# DAC_PMOD.net
KiCad netlist of a schematic drawn in EAGLE
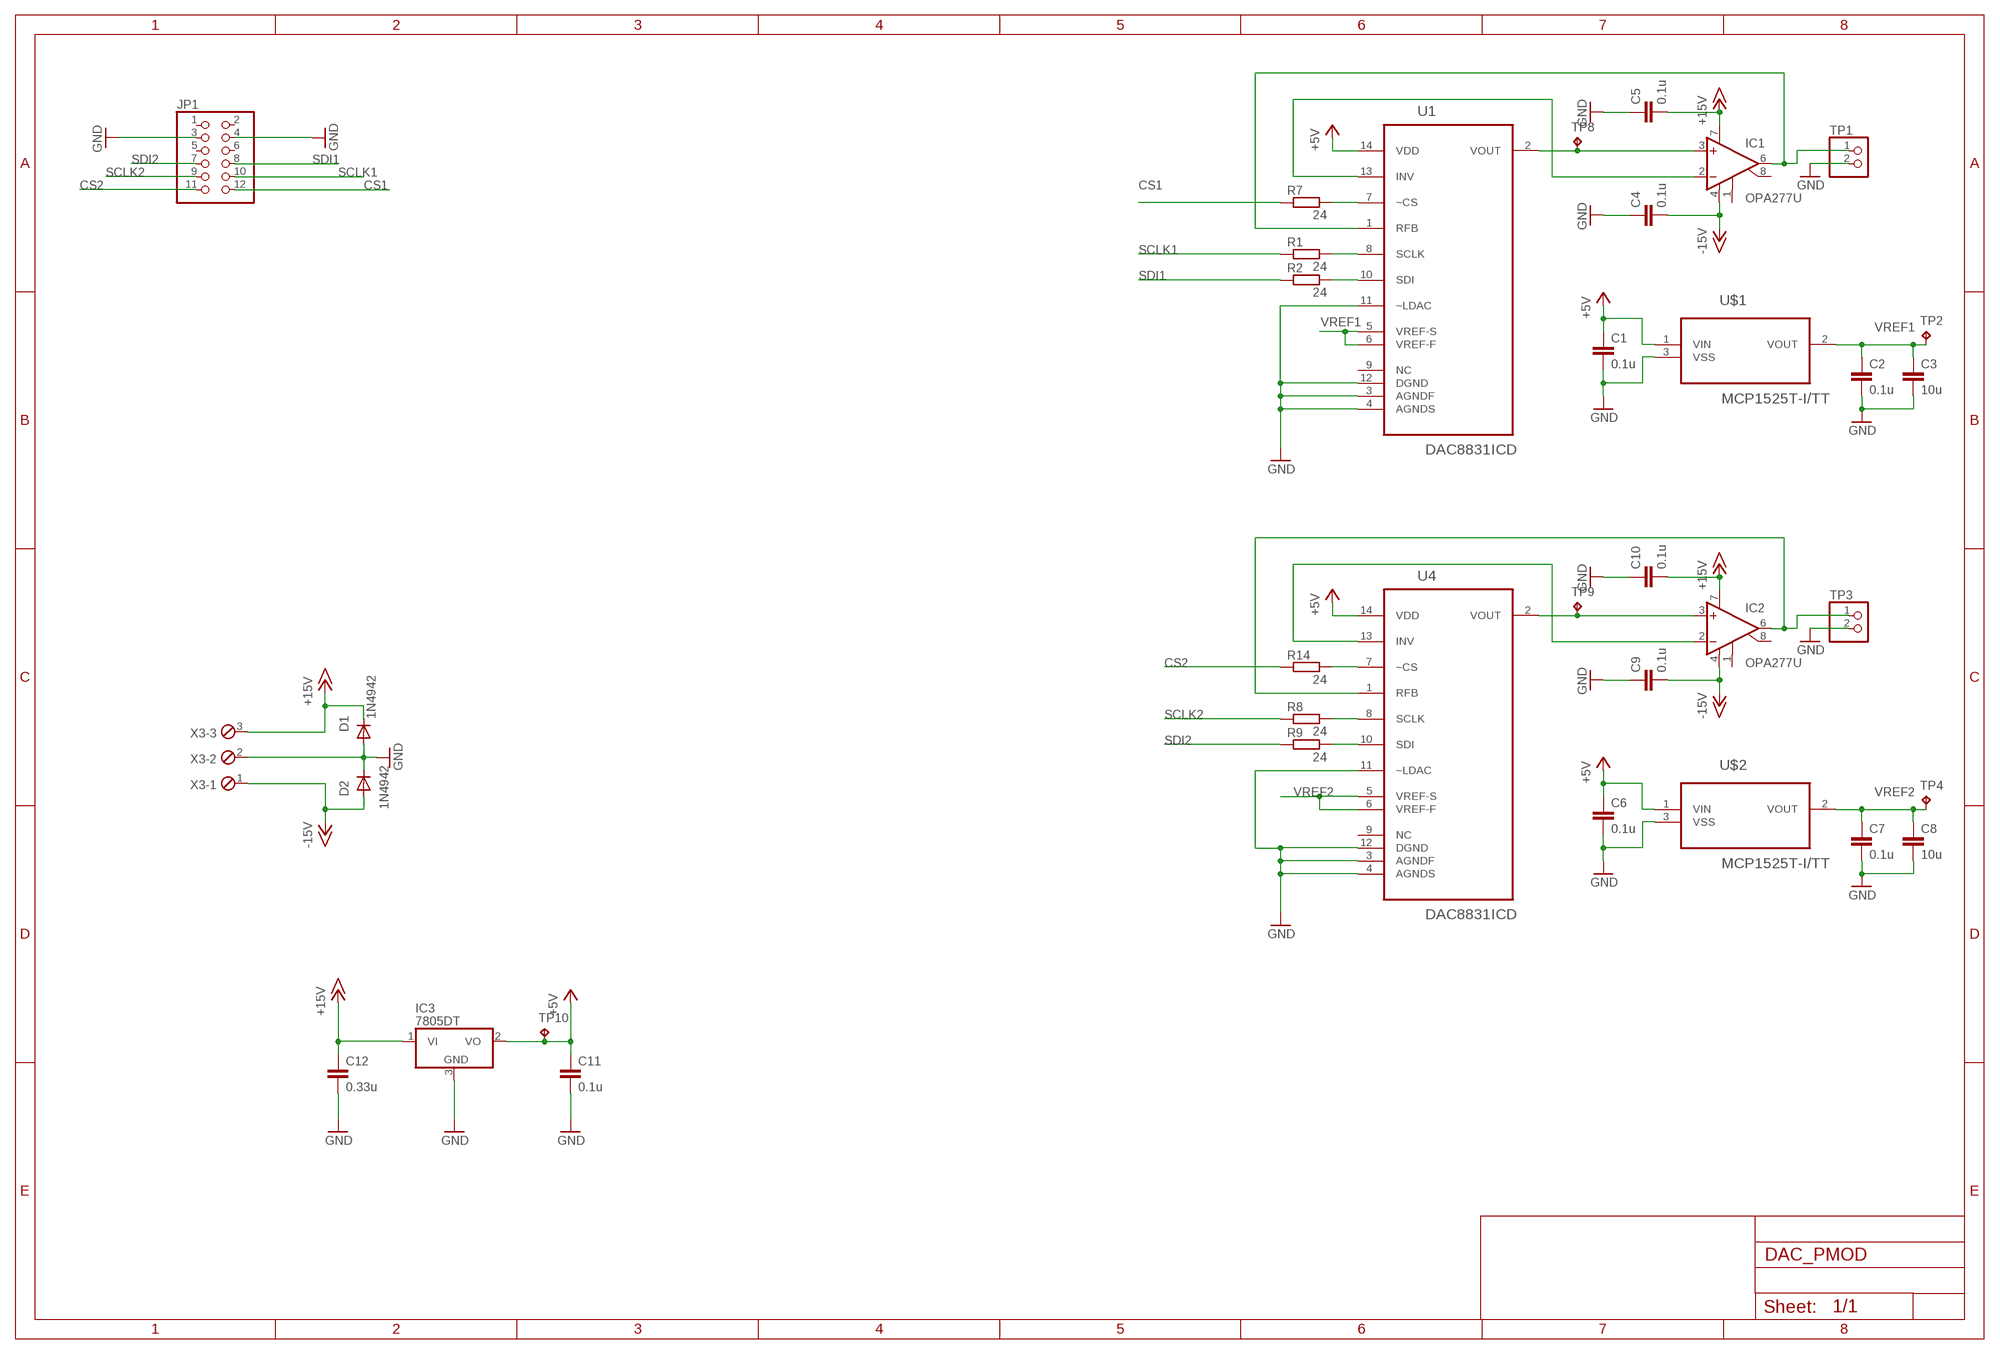
[diagram p0: schematic, sheet 1]

(export (version "E")
  (design (tool "Eeschema 10.0.6"))
  (components
    (comp (ref "C1")
      (value "0.1u")
      (footprint "eagle-import:C0603")
      (libsource (lib "eagle-import") (part "C-EUC0603"))
    )
    (comp (ref "C2")
      (value "0.1u")
      (footprint "eagle-import:C0603")
      (libsource (lib "eagle-import") (part "C-EUC0603"))
    )
    (comp (ref "C3")
      (value "10u")
      (footprint "eagle-import:C0603")
      (libsource (lib "eagle-import") (part "C-EUC0603"))
    )
    (comp (ref "C4")
      (value "0.1u")
      (footprint "eagle-import:C0603")
      (libsource (lib "eagle-import") (part "C-EUC0603"))
    )
    (comp (ref "C5")
      (value "0.1u")
      (footprint "eagle-import:C0603")
      (libsource (lib "eagle-import") (part "C-EUC0603"))
    )
    (comp (ref "C6")
      (value "0.1u")
      (footprint "eagle-import:C0603")
      (libsource (lib "eagle-import") (part "C-EUC0603"))
    )
    (comp (ref "C7")
      (value "0.1u")
      (footprint "eagle-import:C0603")
      (libsource (lib "eagle-import") (part "C-EUC0603"))
    )
    (comp (ref "C8")
      (value "10u")
      (footprint "eagle-import:C0603")
      (libsource (lib "eagle-import") (part "C-EUC0603"))
    )
    (comp (ref "C9")
      (value "0.1u")
      (footprint "eagle-import:C0603")
      (libsource (lib "eagle-import") (part "C-EUC0603"))
    )
    (comp (ref "C10")
      (value "0.1u")
      (footprint "eagle-import:C0603")
      (libsource (lib "eagle-import") (part "C-EUC0603"))
    )
    (comp (ref "C11")
      (value "0.1u")
      (footprint "eagle-import:C0603")
      (libsource (lib "eagle-import") (part "C-EUC0603"))
    )
    (comp (ref "C12")
      (value "0.33u")
      (footprint "eagle-import:C0603")
      (libsource (lib "eagle-import") (part "C-EUC0603"))
    )
    (comp (ref "D1")
      (value "1N4942")
      (footprint "eagle-import:DO41-10")
      (libsource (lib "eagle-import") (part "1N4942"))
    )
    (comp (ref "D2")
      (value "1N4942")
      (footprint "eagle-import:DO41-10")
      (libsource (lib "eagle-import") (part "1N4942"))
    )
    (comp (ref "IC1")
      (value "OPA277U")
      (footprint "eagle-import:SO08")
      (libsource (lib "eagle-import") (part "OPA277U"))
    )
    (comp (ref "IC2")
      (value "OPA277U")
      (footprint "eagle-import:SO08")
      (libsource (lib "eagle-import") (part "OPA277U"))
    )
    (comp (ref "IC3")
      (value "7805DT")
      (footprint "eagle-import:TO252")
      (libsource (lib "eagle-import") (part "78DT05"))
    )
    (comp (ref "JP1")
      (value "PINHD-2X6/90")
      (footprint "eagle-import:2X06_90")
      (libsource (lib "eagle-import") (part "PINHD-2X6/90"))
    )
    (comp (ref "R1")
      (value "24")
      (footprint "eagle-import:R0603")
      (libsource (lib "eagle-import") (part "R-EU_R0603"))
    )
    (comp (ref "R2")
      (value "24")
      (footprint "eagle-import:R0603")
      (libsource (lib "eagle-import") (part "R-EU_R0603"))
    )
    (comp (ref "R7")
      (value "24")
      (footprint "eagle-import:R0603")
      (libsource (lib "eagle-import") (part "R-EU_R0603"))
    )
    (comp (ref "R8")
      (value "24")
      (footprint "eagle-import:R0603")
      (libsource (lib "eagle-import") (part "R-EU_R0603"))
    )
    (comp (ref "R9")
      (value "24")
      (footprint "eagle-import:R0603")
      (libsource (lib "eagle-import") (part "R-EU_R0603"))
    )
    (comp (ref "R14")
      (value "24")
      (footprint "eagle-import:R0603")
      (libsource (lib "eagle-import") (part "R-EU_R0603"))
    )
    (comp (ref "TP1")
      (value "PINHD-1X2")
      (footprint "eagle-import:1X02")
      (libsource (lib "eagle-import") (part "PINHD-1X2"))
    )
    (comp (ref "TP2")
      (value "TPB1,27")
      (footprint "eagle-import:B1,27")
      (libsource (lib "eagle-import") (part "TPB1,27"))
    )
    (comp (ref "TP3")
      (value "PINHD-1X2")
      (footprint "eagle-import:1X02")
      (libsource (lib "eagle-import") (part "PINHD-1X2"))
    )
    (comp (ref "TP4")
      (value "TPB1,27")
      (footprint "eagle-import:B1,27")
      (libsource (lib "eagle-import") (part "TPB1,27"))
    )
    (comp (ref "TP8")
      (value "TPB1,27")
      (footprint "eagle-import:B1,27")
      (libsource (lib "eagle-import") (part "TPB1,27"))
    )
    (comp (ref "TP9")
      (value "TPB1,27")
      (footprint "eagle-import:B1,27")
      (libsource (lib "eagle-import") (part "TPB1,27"))
    )
    (comp (ref "TP10")
      (value "TPB1,27")
      (footprint "eagle-import:B1,27")
      (libsource (lib "eagle-import") (part "TPB1,27"))
    )
    (comp (ref "U$1")
      (value "MCP1525T-I/TT")
      (footprint "eagle-import:SOT96P237X112-3N")
      (libsource (lib "eagle-import") (part "MCP1525T-I/TT"))
    )
    (comp (ref "U$2")
      (value "MCP1525T-I/TT")
      (footprint "eagle-import:SOT96P237X112-3N")
      (libsource (lib "eagle-import") (part "MCP1525T-I/TT"))
    )
    (comp (ref "U1")
      (value "DAC8831ICD")
      (footprint "eagle-import:SOIC127P600X175-14N")
      (libsource (lib "eagle-import") (part "DAC8831ICD"))
    )
    (comp (ref "U4")
      (value "DAC8831ICD")
      (footprint "eagle-import:SOIC127P600X175-14N")
      (libsource (lib "eagle-import") (part "DAC8831ICD"))
    )
    (comp (ref "X3")
      (value "MPT3")
      (footprint "eagle-import:3POL254")
      (libsource (lib "eagle-import") (part "MPT3"))
    )
  )
  (nets
    (net (code "1") (name "+5V") (class "Default")
      (node (ref "C1") (pin "1") (pinfunction "1_1") (pintype "passive"))
      (node (ref "C11") (pin "1") (pinfunction "1_1") (pintype "passive"))
      (node (ref "C6") (pin "1") (pinfunction "1_1") (pintype "passive"))
      (node (ref "IC3") (pin "2") (pinfunction "VO_2") (pintype "passive"))
      (node (ref "TP10") (pin "TP") (pinfunction "TP_TP") (pintype "input"))
      (node (ref "U$1") (pin "1") (pinfunction "VIN_1") (pintype "power_in"))
      (node (ref "U$2") (pin "1") (pinfunction "VIN_1") (pintype "power_in"))
      (node (ref "U1") (pin "14") (pinfunction "VDD_14") (pintype "power_in"))
      (node (ref "U4") (pin "14") (pinfunction "VDD_14") (pintype "power_in"))
    )
    (net (code "2") (name "+15V") (class "Default")
      (node (ref "C10") (pin "2") (pinfunction "2_2") (pintype "passive"))
      (node (ref "C12") (pin "1") (pinfunction "1_1") (pintype "passive"))
      (node (ref "C5") (pin "2") (pinfunction "2_2") (pintype "passive"))
      (node (ref "D1") (pin "C") (pinfunction "C_C") (pintype "passive"))
      (node (ref "IC1") (pin "7") (pinfunction "V+_7") (pintype "power_in"))
      (node (ref "IC2") (pin "7") (pinfunction "V+_7") (pintype "power_in"))
      (node (ref "IC3") (pin "1") (pinfunction "VI_1") (pintype "input"))
      (node (ref "X3") (pin "3") (pinfunction "1_3") (pintype "passive"))
    )
    (net (code "3") (name "-15V") (class "Default")
      (node (ref "C4") (pin "2") (pinfunction "2_2") (pintype "passive"))
      (node (ref "C9") (pin "2") (pinfunction "2_2") (pintype "passive"))
      (node (ref "D2") (pin "A") (pinfunction "A_A") (pintype "passive"))
      (node (ref "IC1") (pin "4") (pinfunction "V-_4") (pintype "power_in"))
      (node (ref "IC2") (pin "4") (pinfunction "V-_4") (pintype "power_in"))
      (node (ref "X3") (pin "1") (pinfunction "1_1") (pintype "passive"))
    )
    (net (code "4") (name "/CS1") (class "Default")
      (node (ref "JP1") (pin "12") (pinfunction "12_12") (pintype "passive"))
      (node (ref "R7") (pin "1") (pinfunction "1_1") (pintype "passive"))
    )
    (net (code "5") (name "/CS2") (class "Default")
      (node (ref "JP1") (pin "11") (pinfunction "11_11") (pintype "passive"))
      (node (ref "R14") (pin "1") (pinfunction "1_1") (pintype "passive"))
    )
    (net (code "6") (name "/SCLK1") (class "Default")
      (node (ref "JP1") (pin "10") (pinfunction "10_10") (pintype "passive"))
      (node (ref "R1") (pin "1") (pinfunction "1_1") (pintype "passive"))
    )
    (net (code "7") (name "/SCLK2") (class "Default")
      (node (ref "JP1") (pin "9") (pinfunction "9_9") (pintype "passive"))
      (node (ref "R8") (pin "1") (pinfunction "1_1") (pintype "passive"))
    )
    (net (code "8") (name "/SDI1") (class "Default")
      (node (ref "JP1") (pin "8") (pinfunction "8_8") (pintype "passive"))
      (node (ref "R2") (pin "1") (pinfunction "1_1") (pintype "passive"))
    )
    (net (code "9") (name "/SDI2") (class "Default")
      (node (ref "JP1") (pin "7") (pinfunction "7_7") (pintype "passive"))
      (node (ref "R9") (pin "1") (pinfunction "1_1") (pintype "passive"))
    )
    (net (code "10") (name "/VREF1") (class "Default")
      (node (ref "C2") (pin "1") (pinfunction "1_1") (pintype "passive"))
      (node (ref "C3") (pin "1") (pinfunction "1_1") (pintype "passive"))
      (node (ref "TP2") (pin "TP") (pinfunction "TP_TP") (pintype "input"))
      (node (ref "U$1") (pin "2") (pinfunction "VOUT_2") (pintype "output"))
      (node (ref "U1") (pin "5") (pinfunction "VREF-S_5") (pintype "input"))
      (node (ref "U1") (pin "6") (pinfunction "VREF-F_6") (pintype "input"))
    )
    (net (code "11") (name "/VREF2") (class "Default")
      (node (ref "C7") (pin "1") (pinfunction "1_1") (pintype "passive"))
      (node (ref "C8") (pin "1") (pinfunction "1_1") (pintype "passive"))
      (node (ref "TP4") (pin "TP") (pinfunction "TP_TP") (pintype "input"))
      (node (ref "U$2") (pin "2") (pinfunction "VOUT_2") (pintype "output"))
      (node (ref "U4") (pin "5") (pinfunction "VREF-S_5") (pintype "input"))
      (node (ref "U4") (pin "6") (pinfunction "VREF-F_6") (pintype "input"))
    )
    (net (code "12") (name "GND") (class "Default")
      (node (ref "C1") (pin "2") (pinfunction "2_2") (pintype "passive"))
      (node (ref "C10") (pin "1") (pinfunction "1_1") (pintype "passive"))
      (node (ref "C11") (pin "2") (pinfunction "2_2") (pintype "passive"))
      (node (ref "C12") (pin "2") (pinfunction "2_2") (pintype "passive"))
      (node (ref "C2") (pin "2") (pinfunction "2_2") (pintype "passive"))
      (node (ref "C3") (pin "2") (pinfunction "2_2") (pintype "passive"))
      (node (ref "C4") (pin "1") (pinfunction "1_1") (pintype "passive"))
      (node (ref "C5") (pin "1") (pinfunction "1_1") (pintype "passive"))
      (node (ref "C6") (pin "2") (pinfunction "2_2") (pintype "passive"))
      (node (ref "C7") (pin "2") (pinfunction "2_2") (pintype "passive"))
      (node (ref "C8") (pin "2") (pinfunction "2_2") (pintype "passive"))
      (node (ref "C9") (pin "1") (pinfunction "1_1") (pintype "passive"))
      (node (ref "D1") (pin "A") (pinfunction "A_A") (pintype "passive"))
      (node (ref "D2") (pin "C") (pinfunction "C_C") (pintype "passive"))
      (node (ref "IC3") (pin "3") (pinfunction "GND_3") (pintype "passive"))
      (node (ref "JP1") (pin "3") (pinfunction "3_3") (pintype "passive"))
      (node (ref "JP1") (pin "4") (pinfunction "4_4") (pintype "passive"))
      (node (ref "TP1") (pin "2") (pinfunction "2_2") (pintype "passive"))
      (node (ref "TP3") (pin "2") (pinfunction "2_2") (pintype "passive"))
      (node (ref "U$1") (pin "3") (pinfunction "VSS_3") (pintype "power_in"))
      (node (ref "U$2") (pin "3") (pinfunction "VSS_3") (pintype "power_in"))
      (node (ref "U1") (pin "11") (pinfunction "~{LDAC}_11") (pintype "input"))
      (node (ref "U1") (pin "12") (pinfunction "DGND_12") (pintype "passive"))
      (node (ref "U1") (pin "3") (pinfunction "AGNDF_3") (pintype "passive"))
      (node (ref "U1") (pin "4") (pinfunction "AGNDS_4") (pintype "passive"))
      (node (ref "U4") (pin "11") (pinfunction "~{LDAC}_11") (pintype "input"))
      (node (ref "U4") (pin "12") (pinfunction "DGND_12") (pintype "passive"))
      (node (ref "U4") (pin "3") (pinfunction "AGNDF_3") (pintype "passive"))
      (node (ref "U4") (pin "4") (pinfunction "AGNDS_4") (pintype "passive"))
      (node (ref "X3") (pin "2") (pinfunction "1_2") (pintype "passive"))
    )
    (net (code "13") (name "Net-(IC1-+IN)") (class "Default")
      (node (ref "IC1") (pin "3") (pinfunction "+IN_3") (pintype "input"))
      (node (ref "TP8") (pin "TP") (pinfunction "TP_TP") (pintype "input"))
      (node (ref "U1") (pin "2") (pinfunction "VOUT_2") (pintype "output"))
    )
    (net (code "14") (name "Net-(IC1--IN)") (class "Default")
      (node (ref "IC1") (pin "2") (pinfunction "-IN_2") (pintype "input"))
      (node (ref "U1") (pin "13") (pinfunction "INV_13") (pintype "passive"))
    )
    (net (code "15") (name "Net-(IC1-OUT)") (class "Default")
      (node (ref "IC1") (pin "6") (pinfunction "OUT_6") (pintype "output"))
      (node (ref "TP1") (pin "1") (pinfunction "1_1") (pintype "passive"))
      (node (ref "U1") (pin "1") (pinfunction "RFB_1") (pintype "input"))
    )
    (net (code "16") (name "Net-(IC2-+IN)") (class "Default")
      (node (ref "IC2") (pin "3") (pinfunction "+IN_3") (pintype "input"))
      (node (ref "TP9") (pin "TP") (pinfunction "TP_TP") (pintype "input"))
      (node (ref "U4") (pin "2") (pinfunction "VOUT_2") (pintype "output"))
    )
    (net (code "17") (name "Net-(IC2--IN)") (class "Default")
      (node (ref "IC2") (pin "2") (pinfunction "-IN_2") (pintype "input"))
      (node (ref "U4") (pin "13") (pinfunction "INV_13") (pintype "passive"))
    )
    (net (code "18") (name "Net-(IC2-OUT)") (class "Default")
      (node (ref "IC2") (pin "6") (pinfunction "OUT_6") (pintype "output"))
      (node (ref "TP3") (pin "1") (pinfunction "1_1") (pintype "passive"))
      (node (ref "U4") (pin "1") (pinfunction "RFB_1") (pintype "input"))
    )
    (net (code "19") (name "Net-(U1-SCLK)") (class "Default")
      (node (ref "R1") (pin "2") (pinfunction "2_2") (pintype "passive"))
      (node (ref "U1") (pin "8") (pinfunction "SCLK_8") (pintype "input"))
    )
    (net (code "20") (name "Net-(U1-SDI)") (class "Default")
      (node (ref "R2") (pin "2") (pinfunction "2_2") (pintype "passive"))
      (node (ref "U1") (pin "10") (pinfunction "SDI_10") (pintype "input"))
    )
    (net (code "21") (name "Net-(U1-~{CS})") (class "Default")
      (node (ref "R7") (pin "2") (pinfunction "2_2") (pintype "passive"))
      (node (ref "U1") (pin "7") (pinfunction "~{CS}_7") (pintype "input"))
    )
    (net (code "22") (name "Net-(U4-SCLK)") (class "Default")
      (node (ref "R8") (pin "2") (pinfunction "2_2") (pintype "passive"))
      (node (ref "U4") (pin "8") (pinfunction "SCLK_8") (pintype "input"))
    )
    (net (code "23") (name "Net-(U4-SDI)") (class "Default")
      (node (ref "R9") (pin "2") (pinfunction "2_2") (pintype "passive"))
      (node (ref "U4") (pin "10") (pinfunction "SDI_10") (pintype "input"))
    )
    (net (code "24") (name "Net-(U4-~{CS})") (class "Default")
      (node (ref "R14") (pin "2") (pinfunction "2_2") (pintype "passive"))
      (node (ref "U4") (pin "7") (pinfunction "~{CS}_7") (pintype "input"))
    )
    (net (code "25") (name "unconnected-(IC1-CMP1-Pad1)") (class "Default")
      (node (ref "IC1") (pin "1") (pinfunction "CMP1_1") (pintype "passive"))
    )
    (net (code "26") (name "unconnected-(IC1-CMP2-Pad8)") (class "Default")
      (node (ref "IC1") (pin "8") (pinfunction "CMP2_8") (pintype "passive"))
    )
    (net (code "27") (name "unconnected-(IC2-CMP1-Pad1)") (class "Default")
      (node (ref "IC2") (pin "1") (pinfunction "CMP1_1") (pintype "passive"))
    )
    (net (code "28") (name "unconnected-(IC2-CMP2-Pad8)") (class "Default")
      (node (ref "IC2") (pin "8") (pinfunction "CMP2_8") (pintype "passive"))
    )
    (net (code "29") (name "unconnected-(JP1-Pad1)") (class "Default")
      (node (ref "JP1") (pin "1") (pinfunction "1_1") (pintype "passive"))
    )
    (net (code "30") (name "unconnected-(JP1-Pad2)") (class "Default")
      (node (ref "JP1") (pin "2") (pinfunction "2_2") (pintype "passive"))
    )
    (net (code "31") (name "unconnected-(JP1-Pad5)") (class "Default")
      (node (ref "JP1") (pin "5") (pinfunction "5_5") (pintype "passive"))
    )
    (net (code "32") (name "unconnected-(JP1-Pad6)") (class "Default")
      (node (ref "JP1") (pin "6") (pinfunction "6_6") (pintype "passive"))
    )
    (net (code "33") (name "unconnected-(U1-NC-Pad9)") (class "Default")
      (node (ref "U1") (pin "9") (pinfunction "NC_9") (pintype "no_connect"))
    )
    (net (code "34") (name "unconnected-(U4-NC-Pad9)") (class "Default")
      (node (ref "U4") (pin "9") (pinfunction "NC_9") (pintype "no_connect"))
    )
  )
)
